# module-schematic.net
KiCad netlist of a schematic drawn in EAGLE
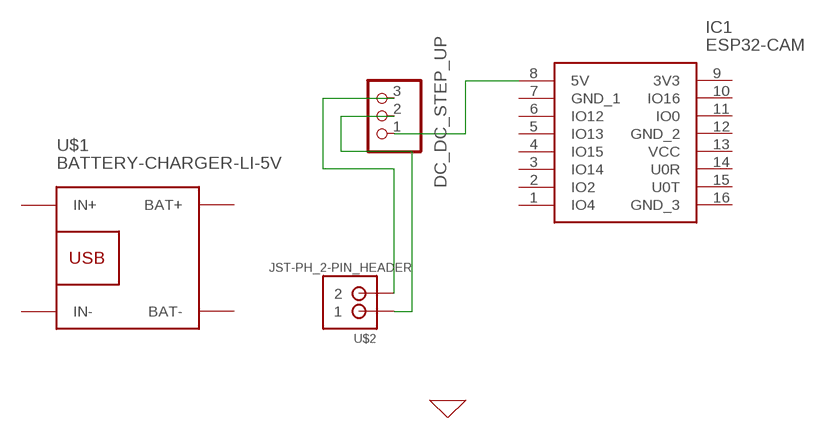
[diagram p0: schematic, sheet 1]

(export (version "E")
  (design (tool "Eeschema 10.0.6"))
  (components
    (comp (ref "DC_DC_STEP_UP")
      (value "PINHD-1X3")
      (footprint "eagle-import:1X03")
      (libsource (lib "eagle-import") (part "PINHD-1X3"))
    )
    (comp (ref "IC1")
      (value "ESP32-CAM")
      (footprint "eagle-import:ESP32CAM")
      (libsource (lib "eagle-import") (part "ESP32-CAM"))
    )
    (comp (ref "U$1")
      (value "BATTERY-CHARGER-LI-5V")
      (footprint "eagle-import:BATTERY-CHARGER-LI-5V")
      (libsource (lib "eagle-import") (part "BATTERY-CHARGER-LI-5V"))
    )
    (comp (ref "U$2")
      (value "JST-PH_2-PIN_HEADER")
      (footprint "eagle-import:JST_B2B-PH_HEADER")
      (libsource (lib "eagle-import") (part "JST-PH_2-PIN_HEADER"))
    )
  )
  (nets
    (net (code "2") (name "Net-(IC1-5V)") (class "Default")
      (node (ref "DC_DC_STEP_UP") (pin "1") (pinfunction "1_1") (pintype "passive"))
      (node (ref "IC1") (pin "8") (pinfunction "5V_8") (pintype "bidirectional"))
    )
    (net (code "3") (name "Net-(U$2-1)") (class "Default")
      (node (ref "DC_DC_STEP_UP") (pin "2") (pinfunction "2_2") (pintype "passive"))
      (node (ref "U$2") (pin "P1") (pinfunction "1_P1") (pintype "bidirectional"))
    )
    (net (code "4") (name "Net-(U$2-2)") (class "Default")
      (node (ref "DC_DC_STEP_UP") (pin "3") (pinfunction "3_3") (pintype "passive"))
      (node (ref "U$2") (pin "P2") (pinfunction "2_P2") (pintype "bidirectional"))
    )
    (net (code "5") (name "unconnected-(IC1-3V3-Pad9)") (class "Default")
      (node (ref "IC1") (pin "9") (pinfunction "3V3_9") (pintype "bidirectional"))
    )
    (net (code "6") (name "unconnected-(IC1-GND_1-Pad7)") (class "Default")
      (node (ref "IC1") (pin "7") (pinfunction "GND_1_7") (pintype "bidirectional"))
    )
    (net (code "7") (name "unconnected-(IC1-GND_2-Pad12)") (class "Default")
      (node (ref "IC1") (pin "12") (pinfunction "GND_2_12") (pintype "bidirectional"))
    )
    (net (code "8") (name "unconnected-(IC1-GND_3-Pad16)") (class "Default")
      (node (ref "IC1") (pin "16") (pinfunction "GND_3_16") (pintype "bidirectional"))
    )
    (net (code "9") (name "unconnected-(IC1-IO0-Pad11)") (class "Default")
      (node (ref "IC1") (pin "11") (pinfunction "IO0_11") (pintype "bidirectional"))
    )
    (net (code "10") (name "unconnected-(IC1-IO2-Pad2)") (class "Default")
      (node (ref "IC1") (pin "2") (pinfunction "IO2_2") (pintype "bidirectional"))
    )
    (net (code "11") (name "unconnected-(IC1-IO4-Pad1)") (class "Default")
      (node (ref "IC1") (pin "1") (pinfunction "IO4_1") (pintype "bidirectional"))
    )
    (net (code "12") (name "unconnected-(IC1-IO12-Pad6)") (class "Default")
      (node (ref "IC1") (pin "6") (pinfunction "IO12_6") (pintype "bidirectional"))
    )
    (net (code "13") (name "unconnected-(IC1-IO13-Pad5)") (class "Default")
      (node (ref "IC1") (pin "5") (pinfunction "IO13_5") (pintype "bidirectional"))
    )
    (net (code "14") (name "unconnected-(IC1-IO14-Pad3)") (class "Default")
      (node (ref "IC1") (pin "3") (pinfunction "IO14_3") (pintype "bidirectional"))
    )
    (net (code "15") (name "unconnected-(IC1-IO15-Pad4)") (class "Default")
      (node (ref "IC1") (pin "4") (pinfunction "IO15_4") (pintype "bidirectional"))
    )
    (net (code "16") (name "unconnected-(IC1-IO16-Pad10)") (class "Default")
      (node (ref "IC1") (pin "10") (pinfunction "IO16_10") (pintype "bidirectional"))
    )
    (net (code "17") (name "unconnected-(IC1-U0R-Pad14)") (class "Default")
      (node (ref "IC1") (pin "14") (pinfunction "U0R_14") (pintype "bidirectional"))
    )
    (net (code "18") (name "unconnected-(IC1-U0T-Pad15)") (class "Default")
      (node (ref "IC1") (pin "15") (pinfunction "U0T_15") (pintype "bidirectional"))
    )
    (net (code "19") (name "unconnected-(IC1-VCC-Pad13)") (class "Default")
      (node (ref "IC1") (pin "13") (pinfunction "VCC_13") (pintype "bidirectional"))
    )
    (net (code "20") (name "unconnected-(U$1-PadBAT+)") (class "Default")
      (node (ref "U$1") (pin "BAT+") (pinfunction "BAT+_BAT+") (pintype "bidirectional"))
    )
    (net (code "21") (name "unconnected-(U$1-PadBAT-)") (class "Default")
      (node (ref "U$1") (pin "BAT-") (pinfunction "BAT-_BAT-") (pintype "bidirectional"))
    )
    (net (code "22") (name "unconnected-(U$1-PadIN+)") (class "Default")
      (node (ref "U$1") (pin "IN+") (pinfunction "IN+_IN+") (pintype "bidirectional"))
    )
    (net (code "23") (name "unconnected-(U$1-PadIN-)") (class "Default")
      (node (ref "U$1") (pin "IN-") (pinfunction "IN-_IN-") (pintype "bidirectional"))
    )
  )
)
